# LEDs.net
KiCad netlist of a schematic drawn in Altium Designer
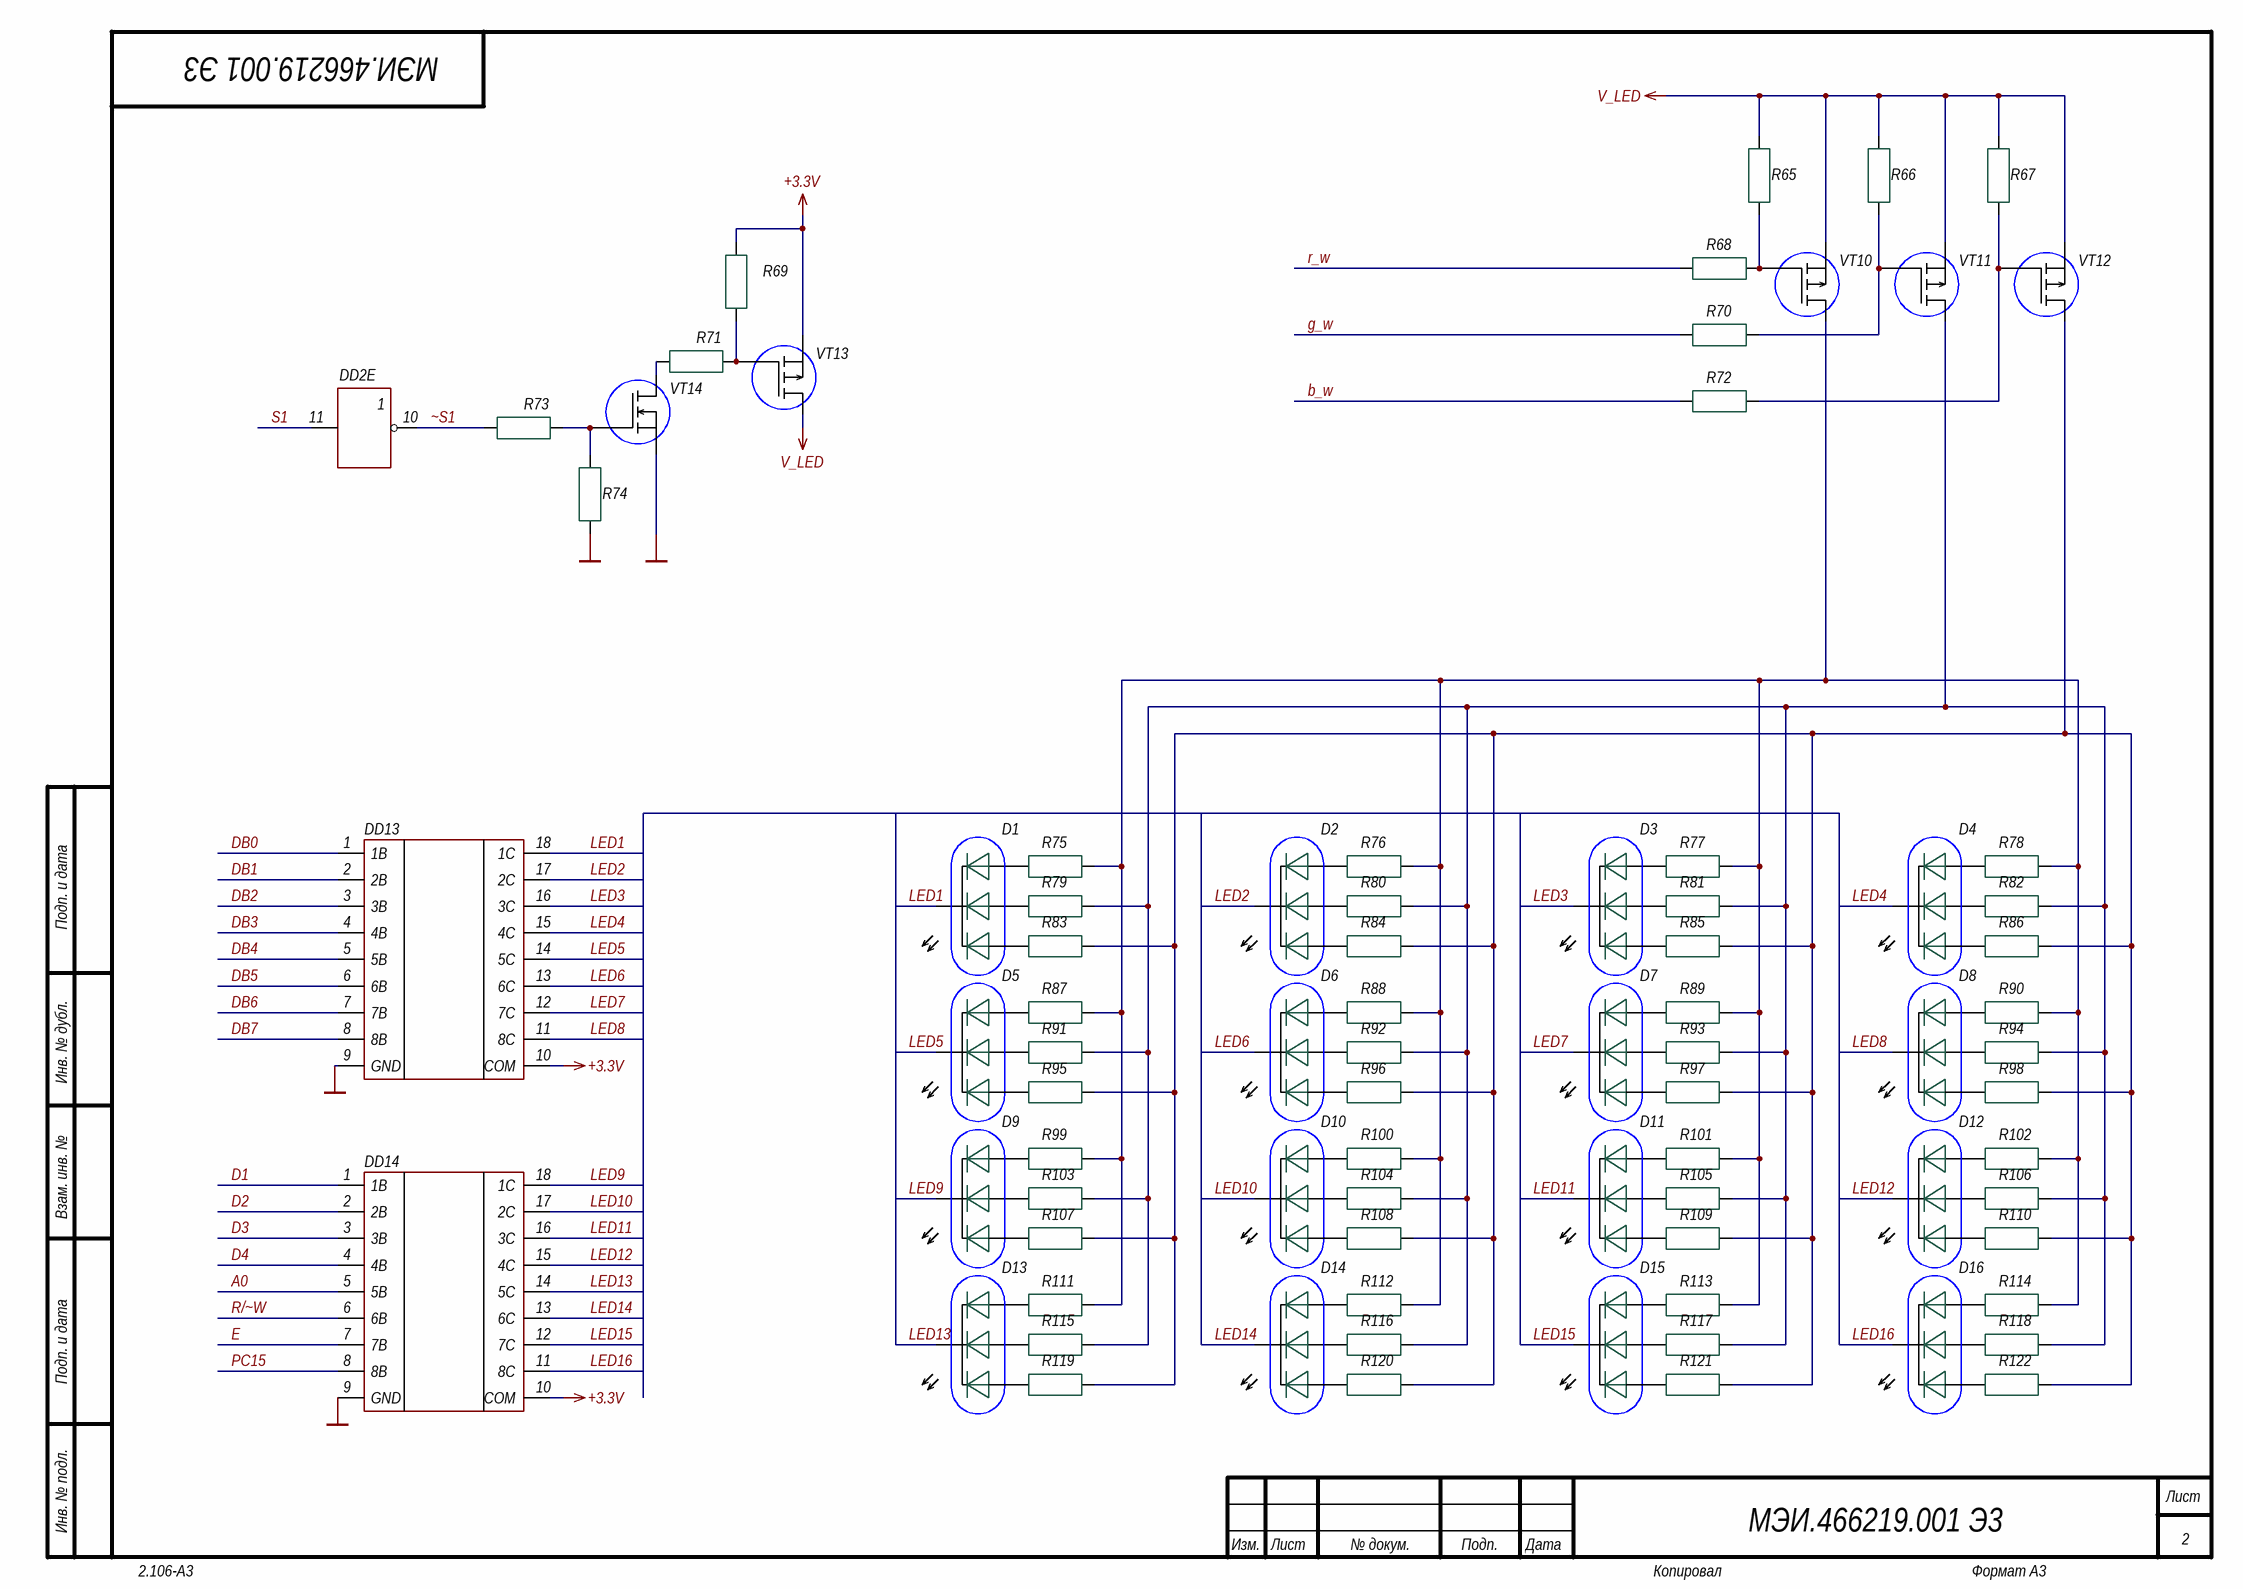
[diagram p0: LEDs.SchDoc]

(export (version "E")
  (design (tool "Eeschema 10.0.6"))
  (components
    (comp (ref "D1")
      (value "FYLS-5050RGBC")
      (footprint "LeSta:SOP6LED")
      (description "RGB LED")
      (libsource (lib "LeSta") (part "FYLS-5050RGBC"))
    )
    (comp (ref "D2")
      (value "FYLS-5050RGBC")
      (footprint "LeSta:SOP6LED")
      (description "RGB LED")
      (libsource (lib "LeSta") (part "FYLS-5050RGBC"))
    )
    (comp (ref "D3")
      (value "FYLS-5050RGBC")
      (footprint "LeSta:SOP6LED")
      (description "RGB LED")
      (libsource (lib "LeSta") (part "FYLS-5050RGBC"))
    )
    (comp (ref "D4")
      (value "FYLS-5050RGBC")
      (footprint "LeSta:SOP6LED")
      (description "RGB LED")
      (libsource (lib "LeSta") (part "FYLS-5050RGBC"))
    )
    (comp (ref "D5")
      (value "FYLS-5050RGBC")
      (footprint "LeSta:SOP6LED")
      (description "RGB LED")
      (libsource (lib "LeSta") (part "FYLS-5050RGBC"))
    )
    (comp (ref "D6")
      (value "FYLS-5050RGBC")
      (footprint "LeSta:SOP6LED")
      (description "RGB LED")
      (libsource (lib "LeSta") (part "FYLS-5050RGBC"))
    )
    (comp (ref "D7")
      (value "FYLS-5050RGBC")
      (footprint "LeSta:SOP6LED")
      (description "RGB LED")
      (libsource (lib "LeSta") (part "FYLS-5050RGBC"))
    )
    (comp (ref "D8")
      (value "FYLS-5050RGBC")
      (footprint "LeSta:SOP6LED")
      (description "RGB LED")
      (libsource (lib "LeSta") (part "FYLS-5050RGBC"))
    )
    (comp (ref "D9")
      (value "FYLS-5050RGBC")
      (footprint "LeSta:SOP6LED")
      (description "RGB LED")
      (libsource (lib "LeSta") (part "FYLS-5050RGBC"))
    )
    (comp (ref "D10")
      (value "FYLS-5050RGBC")
      (footprint "LeSta:SOP6LED")
      (description "RGB LED")
      (libsource (lib "LeSta") (part "FYLS-5050RGBC"))
    )
    (comp (ref "D11")
      (value "FYLS-5050RGBC")
      (footprint "LeSta:SOP6LED")
      (description "RGB LED")
      (libsource (lib "LeSta") (part "FYLS-5050RGBC"))
    )
    (comp (ref "D12")
      (value "FYLS-5050RGBC")
      (footprint "LeSta:SOP6LED")
      (description "RGB LED")
      (libsource (lib "LeSta") (part "FYLS-5050RGBC"))
    )
    (comp (ref "D13")
      (value "FYLS-5050RGBC")
      (footprint "LeSta:SOP6LED")
      (description "RGB LED")
      (libsource (lib "LeSta") (part "FYLS-5050RGBC"))
    )
    (comp (ref "D14")
      (value "FYLS-5050RGBC")
      (footprint "LeSta:SOP6LED")
      (description "RGB LED")
      (libsource (lib "LeSta") (part "FYLS-5050RGBC"))
    )
    (comp (ref "D15")
      (value "FYLS-5050RGBC")
      (footprint "LeSta:SOP6LED")
      (description "RGB LED")
      (libsource (lib "LeSta") (part "FYLS-5050RGBC"))
    )
    (comp (ref "D16")
      (value "FYLS-5050RGBC")
      (footprint "LeSta:SOP6LED")
      (description "RGB LED")
      (libsource (lib "LeSta") (part "FYLS-5050RGBC"))
    )
    (comp (ref "DD2")
      (value "SN74AHCU04DR")
      (footprint "PBL - SMD Packages:SOIC127P780X200-14N")
      (description "HEX invertor")
      (libsource (lib "LeSta") (part "SN74AHCU04"))
    )
    (comp (ref "DD13")
      (value "ULN2803ADW")
      (footprint "LeSta:SOIC127P600-8N")
      (description "Darlington Assembly")
      (libsource (lib "LeSta") (part "ULN2803"))
    )
    (comp (ref "DD14")
      (value "ULN2803ADW")
      (footprint "LeSta:SOIC127P600-8N")
      (description "Darlington Assembly")
      (libsource (lib "LeSta") (part "ULN2803"))
    )
    (comp (ref "R65")
      (value "Thick Film")
      (footprint "RESC1608X55N")
      (description "Resistor SMD chip 10k Ohm 0.1W 1% 0603")
      (fields (field (name "TOLERANCE") "±1%"))
      (libsource (lib "PBL - Resistors") (part "RES_10K_0603_1%"))
    )
    (comp (ref "R66")
      (value "Thick Film")
      (footprint "RESC1608X55N")
      (description "Resistor SMD chip 10k Ohm 0.1W 1% 0603")
      (fields (field (name "TOLERANCE") "±1%"))
      (libsource (lib "PBL - Resistors") (part "RES_10K_0603_1%"))
    )
    (comp (ref "R67")
      (value "Thick Film")
      (footprint "RESC1608X55N")
      (description "Resistor SMD chip 10k Ohm 0.1W 1% 0603")
      (fields (field (name "TOLERANCE") "±1%"))
      (libsource (lib "PBL - Resistors") (part "RES_10K_0603_1%"))
    )
    (comp (ref "R68")
      (value "Thick Film")
      (footprint "RESC1608X55N")
      (description "Resistor SMD chip 470 Ohm 0.1W 5% 0603")
      (fields (field (name "TOLERANCE") "±5%"))
      (libsource (lib "PBL - Resistors") (part "RES_470R_0603_5%"))
    )
    (comp (ref "R69")
      (value "Thick Film")
      (footprint "RESC1608X55N")
      (description "Resistor SMD chip 10k Ohm 0.1W 1% 0603")
      (fields (field (name "TOLERANCE") "±1%"))
      (libsource (lib "PBL - Resistors") (part "RES_10K_0603_1%"))
    )
    (comp (ref "R70")
      (value "Thick Film")
      (footprint "RESC1608X55N")
      (description "Resistor SMD chip 470 Ohm 0.1W 5% 0603")
      (fields (field (name "TOLERANCE") "±5%"))
      (libsource (lib "PBL - Resistors") (part "RES_470R_0603_5%"))
    )
    (comp (ref "R71")
      (value "Thick Film")
      (footprint "RESC1608X55N")
      (description "Resistor SMD chip 470 Ohm 0.1W 5% 0603")
      (fields (field (name "TOLERANCE") "±5%"))
      (libsource (lib "PBL - Resistors") (part "RES_470R_0603_5%"))
    )
    (comp (ref "R72")
      (value "Thick Film")
      (footprint "RESC1608X55N")
      (description "Resistor SMD chip 470 Ohm 0.1W 5% 0603")
      (fields (field (name "TOLERANCE") "±5%"))
      (libsource (lib "PBL - Resistors") (part "RES_470R_0603_5%"))
    )
    (comp (ref "R73")
      (value "Thick Film")
      (footprint "RESC1608X55N")
      (description "Resistor SMD chip 470 Ohm 0.1W 5% 0603")
      (fields (field (name "TOLERANCE") "±5%"))
      (libsource (lib "PBL - Resistors") (part "RES_470R_0603_5%"))
    )
    (comp (ref "R74")
      (value "Thick Film")
      (footprint "RESC1608X55N")
      (description "Resistor SMD chip 10k Ohm 0.1W 1% 0603")
      (fields (field (name "TOLERANCE") "±1%"))
      (libsource (lib "PBL - Resistors") (part "RES_10K_0603_1%"))
    )
    (comp (ref "R75")
      (value "Thick Film")
      (footprint "RESC1608X55N")
      (description "Resistor SMD chip 1,2 kOhm 0.1W 1% 0603")
      (fields (field (name "TOLERANCE") "±1%"))
      (libsource (lib "LearningStand") (part "RES_1K2_0603_1%"))
    )
    (comp (ref "R76")
      (value "Thick Film")
      (footprint "RESC1608X55N")
      (description "Resistor SMD chip 1,2 kOhm 0.1W 1% 0603")
      (fields (field (name "TOLERANCE") "±1%"))
      (libsource (lib "LearningStand") (part "RES_1K2_0603_1%"))
    )
    (comp (ref "R77")
      (value "Thick Film")
      (footprint "RESC1608X55N")
      (description "Resistor SMD chip 1,2 kOhm 0.1W 1% 0603")
      (fields (field (name "TOLERANCE") "±1%"))
      (libsource (lib "LearningStand") (part "RES_1K2_0603_1%"))
    )
    (comp (ref "R78")
      (value "Thick Film")
      (footprint "RESC1608X55N")
      (description "Resistor SMD chip 1,2 kOhm 0.1W 1% 0603")
      (fields (field (name "TOLERANCE") "±1%"))
      (libsource (lib "LearningStand") (part "RES_1K2_0603_1%"))
    )
    (comp (ref "R79")
      (value "Thick Film")
      (footprint "RESC1608X55N")
      (description "Resistor SMD chip 1,2 kOhm 0.1W 1% 0603")
      (fields (field (name "TOLERANCE") "±1%"))
      (libsource (lib "LearningStand") (part "RES_1K2_0603_1%"))
    )
    (comp (ref "R80")
      (value "Thick Film")
      (footprint "RESC1608X55N")
      (description "Resistor SMD chip 1,2 kOhm 0.1W 1% 0603")
      (fields (field (name "TOLERANCE") "±1%"))
      (libsource (lib "LearningStand") (part "RES_1K2_0603_1%"))
    )
    (comp (ref "R81")
      (value "Thick Film")
      (footprint "RESC1608X55N")
      (description "Resistor SMD chip 1,2 kOhm 0.1W 1% 0603")
      (fields (field (name "TOLERANCE") "±1%"))
      (libsource (lib "LearningStand") (part "RES_1K2_0603_1%"))
    )
    (comp (ref "R82")
      (value "Thick Film")
      (footprint "RESC1608X55N")
      (description "Resistor SMD chip 1,2 kOhm 0.1W 1% 0603")
      (fields (field (name "TOLERANCE") "±1%"))
      (libsource (lib "LearningStand") (part "RES_1K2_0603_1%"))
    )
    (comp (ref "R83")
      (value "Thick Film")
      (footprint "RESC1608X55N")
      (description "Resistor SMD chip 1,2 kOhm 0.1W 1% 0603")
      (fields (field (name "TOLERANCE") "±1%"))
      (libsource (lib "LearningStand") (part "RES_1K2_0603_1%"))
    )
    (comp (ref "R84")
      (value "Thick Film")
      (footprint "RESC1608X55N")
      (description "Resistor SMD chip 1,2 kOhm 0.1W 1% 0603")
      (fields (field (name "TOLERANCE") "±1%"))
      (libsource (lib "LearningStand") (part "RES_1K2_0603_1%"))
    )
    (comp (ref "R85")
      (value "Thick Film")
      (footprint "RESC1608X55N")
      (description "Resistor SMD chip 1,2 kOhm 0.1W 1% 0603")
      (fields (field (name "TOLERANCE") "±1%"))
      (libsource (lib "LearningStand") (part "RES_1K2_0603_1%"))
    )
    (comp (ref "R86")
      (value "Thick Film")
      (footprint "RESC1608X55N")
      (description "Resistor SMD chip 1,2 kOhm 0.1W 1% 0603")
      (fields (field (name "TOLERANCE") "±1%"))
      (libsource (lib "LearningStand") (part "RES_1K2_0603_1%"))
    )
    (comp (ref "R87")
      (value "Thick Film")
      (footprint "RESC1608X55N")
      (description "Resistor SMD chip 1,2 kOhm 0.1W 1% 0603")
      (fields (field (name "TOLERANCE") "±1%"))
      (libsource (lib "LearningStand") (part "RES_1K2_0603_1%"))
    )
    (comp (ref "R88")
      (value "Thick Film")
      (footprint "RESC1608X55N")
      (description "Resistor SMD chip 1,2 kOhm 0.1W 1% 0603")
      (fields (field (name "TOLERANCE") "±1%"))
      (libsource (lib "LearningStand") (part "RES_1K2_0603_1%"))
    )
    (comp (ref "R89")
      (value "Thick Film")
      (footprint "RESC1608X55N")
      (description "Resistor SMD chip 1,2 kOhm 0.1W 1% 0603")
      (fields (field (name "TOLERANCE") "±1%"))
      (libsource (lib "LearningStand") (part "RES_1K2_0603_1%"))
    )
    (comp (ref "R90")
      (value "Thick Film")
      (footprint "RESC1608X55N")
      (description "Resistor SMD chip 1,2 kOhm 0.1W 1% 0603")
      (fields (field (name "TOLERANCE") "±1%"))
      (libsource (lib "LearningStand") (part "RES_1K2_0603_1%"))
    )
    (comp (ref "R91")
      (value "Thick Film")
      (footprint "RESC1608X55N")
      (description "Resistor SMD chip 1,2 kOhm 0.1W 1% 0603")
      (fields (field (name "TOLERANCE") "±1%"))
      (libsource (lib "LearningStand") (part "RES_1K2_0603_1%"))
    )
    (comp (ref "R92")
      (value "Thick Film")
      (footprint "RESC1608X55N")
      (description "Resistor SMD chip 1,2 kOhm 0.1W 1% 0603")
      (fields (field (name "TOLERANCE") "±1%"))
      (libsource (lib "LearningStand") (part "RES_1K2_0603_1%"))
    )
    (comp (ref "R93")
      (value "Thick Film")
      (footprint "RESC1608X55N")
      (description "Resistor SMD chip 1,2 kOhm 0.1W 1% 0603")
      (fields (field (name "TOLERANCE") "±1%"))
      (libsource (lib "LearningStand") (part "RES_1K2_0603_1%"))
    )
    (comp (ref "R94")
      (value "Thick Film")
      (footprint "RESC1608X55N")
      (description "Resistor SMD chip 1,2 kOhm 0.1W 1% 0603")
      (fields (field (name "TOLERANCE") "±1%"))
      (libsource (lib "LearningStand") (part "RES_1K2_0603_1%"))
    )
    (comp (ref "R95")
      (value "Thick Film")
      (footprint "RESC1608X55N")
      (description "Resistor SMD chip 1,2 kOhm 0.1W 1% 0603")
      (fields (field (name "TOLERANCE") "±1%"))
      (libsource (lib "LearningStand") (part "RES_1K2_0603_1%"))
    )
    (comp (ref "R96")
      (value "Thick Film")
      (footprint "RESC1608X55N")
      (description "Resistor SMD chip 1,2 kOhm 0.1W 1% 0603")
      (fields (field (name "TOLERANCE") "±1%"))
      (libsource (lib "LearningStand") (part "RES_1K2_0603_1%"))
    )
    (comp (ref "R97")
      (value "Thick Film")
      (footprint "RESC1608X55N")
      (description "Resistor SMD chip 1,2 kOhm 0.1W 1% 0603")
      (fields (field (name "TOLERANCE") "±1%"))
      (libsource (lib "LearningStand") (part "RES_1K2_0603_1%"))
    )
    (comp (ref "R98")
      (value "Thick Film")
      (footprint "RESC1608X55N")
      (description "Resistor SMD chip 1,2 kOhm 0.1W 1% 0603")
      (fields (field (name "TOLERANCE") "±1%"))
      (libsource (lib "LearningStand") (part "RES_1K2_0603_1%"))
    )
    (comp (ref "R99")
      (value "Thick Film")
      (footprint "RESC1608X55N")
      (description "Resistor SMD chip 1,2 kOhm 0.1W 1% 0603")
      (fields (field (name "TOLERANCE") "±1%"))
      (libsource (lib "LearningStand") (part "RES_1K2_0603_1%"))
    )
    (comp (ref "R100")
      (value "Thick Film")
      (footprint "RESC1608X55N")
      (description "Resistor SMD chip 1,2 kOhm 0.1W 1% 0603")
      (fields (field (name "TOLERANCE") "±1%"))
      (libsource (lib "LearningStand") (part "RES_1K2_0603_1%"))
    )
    (comp (ref "R101")
      (value "Thick Film")
      (footprint "RESC1608X55N")
      (description "Resistor SMD chip 1,2 kOhm 0.1W 1% 0603")
      (fields (field (name "TOLERANCE") "±1%"))
      (libsource (lib "LearningStand") (part "RES_1K2_0603_1%"))
    )
    (comp (ref "R102")
      (value "Thick Film")
      (footprint "RESC1608X55N")
      (description "Resistor SMD chip 1,2 kOhm 0.1W 1% 0603")
      (fields (field (name "TOLERANCE") "±1%"))
      (libsource (lib "LearningStand") (part "RES_1K2_0603_1%"))
    )
    (comp (ref "R103")
      (value "Thick Film")
      (footprint "RESC1608X55N")
      (description "Resistor SMD chip 1,2 kOhm 0.1W 1% 0603")
      (fields (field (name "TOLERANCE") "±1%"))
      (libsource (lib "LearningStand") (part "RES_1K2_0603_1%"))
    )
    (comp (ref "R104")
      (value "Thick Film")
      (footprint "RESC1608X55N")
      (description "Resistor SMD chip 1,2 kOhm 0.1W 1% 0603")
      (fields (field (name "TOLERANCE") "±1%"))
      (libsource (lib "LearningStand") (part "RES_1K2_0603_1%"))
    )
    (comp (ref "R105")
      (value "Thick Film")
      (footprint "RESC1608X55N")
      (description "Resistor SMD chip 1,2 kOhm 0.1W 1% 0603")
      (fields (field (name "TOLERANCE") "±1%"))
      (libsource (lib "LearningStand") (part "RES_1K2_0603_1%"))
    )
    (comp (ref "R106")
      (value "Thick Film")
      (footprint "RESC1608X55N")
      (description "Resistor SMD chip 1,2 kOhm 0.1W 1% 0603")
      (fields (field (name "TOLERANCE") "±1%"))
      (libsource (lib "LearningStand") (part "RES_1K2_0603_1%"))
    )
    (comp (ref "R107")
      (value "Thick Film")
      (footprint "RESC1608X55N")
      (description "Resistor SMD chip 1,2 kOhm 0.1W 1% 0603")
      (fields (field (name "TOLERANCE") "±1%"))
      (libsource (lib "LearningStand") (part "RES_1K2_0603_1%"))
    )
    (comp (ref "R108")
      (value "Thick Film")
      (footprint "RESC1608X55N")
      (description "Resistor SMD chip 1,2 kOhm 0.1W 1% 0603")
      (fields (field (name "TOLERANCE") "±1%"))
      (libsource (lib "LearningStand") (part "RES_1K2_0603_1%"))
    )
    (comp (ref "R109")
      (value "Thick Film")
      (footprint "RESC1608X55N")
      (description "Resistor SMD chip 1,2 kOhm 0.1W 1% 0603")
      (fields (field (name "TOLERANCE") "±1%"))
      (libsource (lib "LearningStand") (part "RES_1K2_0603_1%"))
    )
    (comp (ref "R110")
      (value "Thick Film")
      (footprint "RESC1608X55N")
      (description "Resistor SMD chip 1,2 kOhm 0.1W 1% 0603")
      (fields (field (name "TOLERANCE") "±1%"))
      (libsource (lib "LearningStand") (part "RES_1K2_0603_1%"))
    )
    (comp (ref "R111")
      (value "Thick Film")
      (footprint "RESC1608X55N")
      (description "Resistor SMD chip 1,2 kOhm 0.1W 1% 0603")
      (fields (field (name "TOLERANCE") "±1%"))
      (libsource (lib "LearningStand") (part "RES_1K2_0603_1%"))
    )
    (comp (ref "R112")
      (value "Thick Film")
      (footprint "RESC1608X55N")
      (description "Resistor SMD chip 1,2 kOhm 0.1W 1% 0603")
      (fields (field (name "TOLERANCE") "±1%"))
      (libsource (lib "LearningStand") (part "RES_1K2_0603_1%"))
    )
    (comp (ref "R113")
      (value "Thick Film")
      (footprint "RESC1608X55N")
      (description "Resistor SMD chip 1,2 kOhm 0.1W 1% 0603")
      (fields (field (name "TOLERANCE") "±1%"))
      (libsource (lib "LearningStand") (part "RES_1K2_0603_1%"))
    )
    (comp (ref "R114")
      (value "Thick Film")
      (footprint "RESC1608X55N")
      (description "Resistor SMD chip 1,2 kOhm 0.1W 1% 0603")
      (fields (field (name "TOLERANCE") "±1%"))
      (libsource (lib "LearningStand") (part "RES_1K2_0603_1%"))
    )
    (comp (ref "R115")
      (value "Thick Film")
      (footprint "RESC1608X55N")
      (description "Resistor SMD chip 1,2 kOhm 0.1W 1% 0603")
      (fields (field (name "TOLERANCE") "±1%"))
      (libsource (lib "LearningStand") (part "RES_1K2_0603_1%"))
    )
    (comp (ref "R116")
      (value "Thick Film")
      (footprint "RESC1608X55N")
      (description "Resistor SMD chip 1,2 kOhm 0.1W 1% 0603")
      (fields (field (name "TOLERANCE") "±1%"))
      (libsource (lib "LearningStand") (part "RES_1K2_0603_1%"))
    )
    (comp (ref "R117")
      (value "Thick Film")
      (footprint "RESC1608X55N")
      (description "Resistor SMD chip 1,2 kOhm 0.1W 1% 0603")
      (fields (field (name "TOLERANCE") "±1%"))
      (libsource (lib "LearningStand") (part "RES_1K2_0603_1%"))
    )
    (comp (ref "R118")
      (value "Thick Film")
      (footprint "RESC1608X55N")
      (description "Resistor SMD chip 1,2 kOhm 0.1W 1% 0603")
      (fields (field (name "TOLERANCE") "±1%"))
      (libsource (lib "LearningStand") (part "RES_1K2_0603_1%"))
    )
    (comp (ref "R119")
      (value "Thick Film")
      (footprint "RESC1608X55N")
      (description "Resistor SMD chip 1,2 kOhm 0.1W 1% 0603")
      (fields (field (name "TOLERANCE") "±1%"))
      (libsource (lib "LearningStand") (part "RES_1K2_0603_1%"))
    )
    (comp (ref "R120")
      (value "Thick Film")
      (footprint "RESC1608X55N")
      (description "Resistor SMD chip 1,2 kOhm 0.1W 1% 0603")
      (fields (field (name "TOLERANCE") "±1%"))
      (libsource (lib "LearningStand") (part "RES_1K2_0603_1%"))
    )
    (comp (ref "R121")
      (value "Thick Film")
      (footprint "RESC1608X55N")
      (description "Resistor SMD chip 1,2 kOhm 0.1W 1% 0603")
      (fields (field (name "TOLERANCE") "±1%"))
      (libsource (lib "LearningStand") (part "RES_1K2_0603_1%"))
    )
    (comp (ref "R122")
      (value "Thick Film")
      (footprint "RESC1608X55N")
      (description "Resistor SMD chip 1,2 kOhm 0.1W 1% 0603")
      (fields (field (name "TOLERANCE") "±1%"))
      (libsource (lib "LearningStand") (part "RES_1K2_0603_1%"))
    )
    (comp (ref "VT10")
      (value "IRLML2244")
      (footprint "PBL - SMD Packages:SOT23-3-no_check")
      (description "MOSFET P-Channel SMD")
      (libsource (lib "PBL - Transistors") (part "MOSFET_P-CH_IRLML2244TRPbF"))
    )
    (comp (ref "VT11")
      (value "IRLML2244")
      (footprint "PBL - SMD Packages:SOT23-3-no_check")
      (description "MOSFET P-Channel SMD")
      (libsource (lib "PBL - Transistors") (part "MOSFET_P-CH_IRLML2244TRPbF"))
    )
    (comp (ref "VT12")
      (value "IRLML2244")
      (footprint "PBL - SMD Packages:SOT23-3-no_check")
      (description "MOSFET P-Channel SMD")
      (libsource (lib "PBL - Transistors") (part "MOSFET_P-CH_IRLML2244TRPbF"))
    )
    (comp (ref "VT13")
      (value "IRLML2244")
      (footprint "PBL - SMD Packages:SOT23-3-no_check")
      (description "MOSFET P-Channel SMD")
      (libsource (lib "PBL - Transistors") (part "MOSFET_P-CH_IRLML2244TRPbF"))
    )
    (comp (ref "VT14")
      (value "IRLML6244")
      (footprint "PBL - SMD Packages:SOT23-3-no_check")
      (description "MOSFET N-Channel SMD")
      (libsource (lib "PBL - Transistors") (part "MOSFET_N-CH_IRLML6244TRPBF"))
    )
  )
  (nets
    (net (code "1") (name "+3.3V") (class "Default")
      (node (ref "DD13") (pin "10") (pinfunction "COM_10") (pintype "passive"))
      (node (ref "DD14") (pin "10") (pinfunction "COM_10") (pintype "passive"))
      (node (ref "R69") (pin "2") (pinfunction "2_2") (pintype "passive"))
      (node (ref "VT13") (pin "2") (pinfunction "S_2") (pintype "passive"))
    )
    (net (code "2") (name "/A0") (class "Default")
      (node (ref "DD14") (pin "5") (pinfunction "5B_5") (pintype "passive"))
    )
    (net (code "3") (name "/D1") (class "Default")
      (node (ref "DD14") (pin "1") (pinfunction "1B_1") (pintype "passive"))
    )
    (net (code "4") (name "/D2") (class "Default")
      (node (ref "DD14") (pin "2") (pinfunction "2B_2") (pintype "passive"))
    )
    (net (code "5") (name "/D3") (class "Default")
      (node (ref "DD14") (pin "3") (pinfunction "3B_3") (pintype "passive"))
    )
    (net (code "6") (name "/D4") (class "Default")
      (node (ref "DD14") (pin "4") (pinfunction "4B_4") (pintype "passive"))
    )
    (net (code "7") (name "/DB0") (class "Default")
      (node (ref "DD13") (pin "1") (pinfunction "1B_1") (pintype "passive"))
    )
    (net (code "8") (name "/DB1") (class "Default")
      (node (ref "DD13") (pin "2") (pinfunction "2B_2") (pintype "passive"))
    )
    (net (code "9") (name "/DB2") (class "Default")
      (node (ref "DD13") (pin "3") (pinfunction "3B_3") (pintype "passive"))
    )
    (net (code "10") (name "/DB3") (class "Default")
      (node (ref "DD13") (pin "4") (pinfunction "4B_4") (pintype "passive"))
    )
    (net (code "11") (name "/DB4") (class "Default")
      (node (ref "DD13") (pin "5") (pinfunction "5B_5") (pintype "passive"))
    )
    (net (code "12") (name "/DB5") (class "Default")
      (node (ref "DD13") (pin "6") (pinfunction "6B_6") (pintype "passive"))
    )
    (net (code "13") (name "/DB6") (class "Default")
      (node (ref "DD13") (pin "7") (pinfunction "7B_7") (pintype "passive"))
    )
    (net (code "14") (name "/DB7") (class "Default")
      (node (ref "DD13") (pin "8") (pinfunction "8B_8") (pintype "passive"))
    )
    (net (code "15") (name "/E") (class "Default")
      (node (ref "DD14") (pin "7") (pinfunction "7B_7") (pintype "passive"))
    )
    (net (code "16") (name "/LED1") (class "Default")
      (node (ref "D1") (pin "K") (pinfunction "K_K") (pintype "passive"))
      (node (ref "DD13") (pin "18") (pinfunction "1C_18") (pintype "passive"))
    )
    (net (code "17") (name "/LED2") (class "Default")
      (node (ref "D2") (pin "K") (pinfunction "K_K") (pintype "passive"))
      (node (ref "DD13") (pin "17") (pinfunction "2C_17") (pintype "passive"))
    )
    (net (code "18") (name "/LED3") (class "Default")
      (node (ref "D3") (pin "K") (pinfunction "K_K") (pintype "passive"))
      (node (ref "DD13") (pin "16") (pinfunction "3C_16") (pintype "passive"))
    )
    (net (code "19") (name "/LED4") (class "Default")
      (node (ref "D4") (pin "K") (pinfunction "K_K") (pintype "passive"))
      (node (ref "DD13") (pin "15") (pinfunction "4C_15") (pintype "passive"))
    )
    (net (code "20") (name "/LED5") (class "Default")
      (node (ref "D5") (pin "K") (pinfunction "K_K") (pintype "passive"))
      (node (ref "DD13") (pin "14") (pinfunction "5C_14") (pintype "passive"))
    )
    (net (code "21") (name "/LED6") (class "Default")
      (node (ref "D6") (pin "K") (pinfunction "K_K") (pintype "passive"))
      (node (ref "DD13") (pin "13") (pinfunction "6C_13") (pintype "passive"))
    )
    (net (code "22") (name "/LED7") (class "Default")
      (node (ref "D7") (pin "K") (pinfunction "K_K") (pintype "passive"))
      (node (ref "DD13") (pin "12") (pinfunction "7C_12") (pintype "passive"))
    )
    (net (code "23") (name "/LED8") (class "Default")
      (node (ref "D8") (pin "K") (pinfunction "K_K") (pintype "passive"))
      (node (ref "DD13") (pin "11") (pinfunction "8C_11") (pintype "passive"))
    )
    (net (code "24") (name "/LED9") (class "Default")
      (node (ref "D9") (pin "K") (pinfunction "K_K") (pintype "passive"))
      (node (ref "DD14") (pin "18") (pinfunction "1C_18") (pintype "passive"))
    )
    (net (code "25") (name "/LED10") (class "Default")
      (node (ref "D10") (pin "K") (pinfunction "K_K") (pintype "passive"))
      (node (ref "DD14") (pin "17") (pinfunction "2C_17") (pintype "passive"))
    )
    (net (code "26") (name "/LED11") (class "Default")
      (node (ref "D11") (pin "K") (pinfunction "K_K") (pintype "passive"))
      (node (ref "DD14") (pin "16") (pinfunction "3C_16") (pintype "passive"))
    )
    (net (code "27") (name "/LED12") (class "Default")
      (node (ref "D12") (pin "K") (pinfunction "K_K") (pintype "passive"))
      (node (ref "DD14") (pin "15") (pinfunction "4C_15") (pintype "passive"))
    )
    (net (code "28") (name "/LED13") (class "Default")
      (node (ref "D13") (pin "K") (pinfunction "K_K") (pintype "passive"))
      (node (ref "DD14") (pin "14") (pinfunction "5C_14") (pintype "passive"))
    )
    (net (code "29") (name "/LED14") (class "Default")
      (node (ref "D14") (pin "K") (pinfunction "K_K") (pintype "passive"))
      (node (ref "DD14") (pin "13") (pinfunction "6C_13") (pintype "passive"))
    )
    (net (code "30") (name "/LED15") (class "Default")
      (node (ref "D15") (pin "K") (pinfunction "K_K") (pintype "passive"))
      (node (ref "DD14") (pin "12") (pinfunction "7C_12") (pintype "passive"))
    )
    (net (code "31") (name "/LED16") (class "Default")
      (node (ref "D16") (pin "K") (pinfunction "K_K") (pintype "passive"))
      (node (ref "DD14") (pin "11") (pinfunction "8C_11") (pintype "passive"))
    )
    (net (code "32") (name "/PC15") (class "Default")
      (node (ref "DD14") (pin "8") (pinfunction "8B_8") (pintype "passive"))
    )
    (net (code "33") (name "/R{slash}~W") (class "Default")
      (node (ref "DD14") (pin "6") (pinfunction "6B_6") (pintype "passive"))
    )
    (net (code "34") (name "/S1") (class "Default")
      (node (ref "DD2") (pin "11") (pinfunction "5A_11") (pintype "passive"))
    )
    (net (code "35") (name "/b_w") (class "Default")
      (node (ref "R72") (pin "1") (pinfunction "1_1") (pintype "passive"))
    )
    (net (code "36") (name "/g_w") (class "Default")
      (node (ref "R70") (pin "1") (pinfunction "1_1") (pintype "passive"))
    )
    (net (code "37") (name "/r_w") (class "Default")
      (node (ref "R68") (pin "1") (pinfunction "1_1") (pintype "passive"))
    )
    (net (code "38") (name "/~S1") (class "Default")
      (node (ref "DD2") (pin "10") (pinfunction "5Y_10") (pintype "passive"))
      (node (ref "R73") (pin "1") (pinfunction "1_1") (pintype "passive"))
    )
    (net (code "39") (name "GND") (class "Default")
      (node (ref "DD13") (pin "9") (pinfunction "GND_9") (pintype "passive"))
      (node (ref "DD14") (pin "9") (pinfunction "GND_9") (pintype "passive"))
      (node (ref "R74") (pin "1") (pinfunction "1_1") (pintype "passive"))
      (node (ref "VT14") (pin "2") (pinfunction "S_2") (pintype "passive"))
    )
    (net (code "40") (name "Net-(D1-PadAB)") (class "Default")
      (node (ref "D1") (pin "AB") (pinfunction "AB_AB") (pintype "passive"))
      (node (ref "R83") (pin "1") (pinfunction "1_1") (pintype "passive"))
    )
    (net (code "41") (name "Net-(D1-PadAG)") (class "Default")
      (node (ref "D1") (pin "AG") (pinfunction "AG_AG") (pintype "passive"))
      (node (ref "R79") (pin "1") (pinfunction "1_1") (pintype "passive"))
    )
    (net (code "42") (name "Net-(D1-PadAR)") (class "Default")
      (node (ref "D1") (pin "AR") (pinfunction "AR_AR") (pintype "passive"))
      (node (ref "R75") (pin "1") (pinfunction "1_1") (pintype "passive"))
    )
    (net (code "43") (name "Net-(D2-PadAB)") (class "Default")
      (node (ref "D2") (pin "AB") (pinfunction "AB_AB") (pintype "passive"))
      (node (ref "R84") (pin "1") (pinfunction "1_1") (pintype "passive"))
    )
    (net (code "44") (name "Net-(D2-PadAG)") (class "Default")
      (node (ref "D2") (pin "AG") (pinfunction "AG_AG") (pintype "passive"))
      (node (ref "R80") (pin "1") (pinfunction "1_1") (pintype "passive"))
    )
    (net (code "45") (name "Net-(D2-PadAR)") (class "Default")
      (node (ref "D2") (pin "AR") (pinfunction "AR_AR") (pintype "passive"))
      (node (ref "R76") (pin "1") (pinfunction "1_1") (pintype "passive"))
    )
    (net (code "46") (name "Net-(D3-PadAB)") (class "Default")
      (node (ref "D3") (pin "AB") (pinfunction "AB_AB") (pintype "passive"))
      (node (ref "R85") (pin "1") (pinfunction "1_1") (pintype "passive"))
    )
    (net (code "47") (name "Net-(D3-PadAG)") (class "Default")
      (node (ref "D3") (pin "AG") (pinfunction "AG_AG") (pintype "passive"))
      (node (ref "R81") (pin "1") (pinfunction "1_1") (pintype "passive"))
    )
    (net (code "48") (name "Net-(D3-PadAR)") (class "Default")
      (node (ref "D3") (pin "AR") (pinfunction "AR_AR") (pintype "passive"))
      (node (ref "R77") (pin "1") (pinfunction "1_1") (pintype "passive"))
    )
    (net (code "49") (name "Net-(D4-PadAB)") (class "Default")
      (node (ref "D4") (pin "AB") (pinfunction "AB_AB") (pintype "passive"))
      (node (ref "R86") (pin "1") (pinfunction "1_1") (pintype "passive"))
    )
    (net (code "50") (name "Net-(D4-PadAG)") (class "Default")
      (node (ref "D4") (pin "AG") (pinfunction "AG_AG") (pintype "passive"))
      (node (ref "R82") (pin "1") (pinfunction "1_1") (pintype "passive"))
    )
    (net (code "51") (name "Net-(D4-PadAR)") (class "Default")
      (node (ref "D4") (pin "AR") (pinfunction "AR_AR") (pintype "passive"))
      (node (ref "R78") (pin "1") (pinfunction "1_1") (pintype "passive"))
    )
    (net (code "52") (name "Net-(D5-PadAB)") (class "Default")
      (node (ref "D5") (pin "AB") (pinfunction "AB_AB") (pintype "passive"))
      (node (ref "R95") (pin "1") (pinfunction "1_1") (pintype "passive"))
    )
    (net (code "53") (name "Net-(D5-PadAG)") (class "Default")
      (node (ref "D5") (pin "AG") (pinfunction "AG_AG") (pintype "passive"))
      (node (ref "R91") (pin "1") (pinfunction "1_1") (pintype "passive"))
    )
    (net (code "54") (name "Net-(D5-PadAR)") (class "Default")
      (node (ref "D5") (pin "AR") (pinfunction "AR_AR") (pintype "passive"))
      (node (ref "R87") (pin "1") (pinfunction "1_1") (pintype "passive"))
    )
    (net (code "55") (name "Net-(D6-PadAB)") (class "Default")
      (node (ref "D6") (pin "AB") (pinfunction "AB_AB") (pintype "passive"))
      (node (ref "R96") (pin "1") (pinfunction "1_1") (pintype "passive"))
    )
    (net (code "56") (name "Net-(D6-PadAG)") (class "Default")
      (node (ref "D6") (pin "AG") (pinfunction "AG_AG") (pintype "passive"))
      (node (ref "R92") (pin "1") (pinfunction "1_1") (pintype "passive"))
    )
    (net (code "57") (name "Net-(D6-PadAR)") (class "Default")
      (node (ref "D6") (pin "AR") (pinfunction "AR_AR") (pintype "passive"))
      (node (ref "R88") (pin "1") (pinfunction "1_1") (pintype "passive"))
    )
    (net (code "58") (name "Net-(D7-PadAB)") (class "Default")
      (node (ref "D7") (pin "AB") (pinfunction "AB_AB") (pintype "passive"))
      (node (ref "R97") (pin "1") (pinfunction "1_1") (pintype "passive"))
    )
    (net (code "59") (name "Net-(D7-PadAG)") (class "Default")
      (node (ref "D7") (pin "AG") (pinfunction "AG_AG") (pintype "passive"))
      (node (ref "R93") (pin "1") (pinfunction "1_1") (pintype "passive"))
    )
    (net (code "60") (name "Net-(D7-PadAR)") (class "Default")
      (node (ref "D7") (pin "AR") (pinfunction "AR_AR") (pintype "passive"))
      (node (ref "R89") (pin "1") (pinfunction "1_1") (pintype "passive"))
    )
    (net (code "61") (name "Net-(D8-PadAB)") (class "Default")
      (node (ref "D8") (pin "AB") (pinfunction "AB_AB") (pintype "passive"))
      (node (ref "R98") (pin "1") (pinfunction "1_1") (pintype "passive"))
    )
    (net (code "62") (name "Net-(D8-PadAG)") (class "Default")
      (node (ref "D8") (pin "AG") (pinfunction "AG_AG") (pintype "passive"))
      (node (ref "R94") (pin "1") (pinfunction "1_1") (pintype "passive"))
    )
    (net (code "63") (name "Net-(D8-PadAR)") (class "Default")
      (node (ref "D8") (pin "AR") (pinfunction "AR_AR") (pintype "passive"))
      (node (ref "R90") (pin "1") (pinfunction "1_1") (pintype "passive"))
    )
    (net (code "64") (name "Net-(D9-PadAB)") (class "Default")
      (node (ref "D9") (pin "AB") (pinfunction "AB_AB") (pintype "passive"))
      (node (ref "R107") (pin "1") (pinfunction "1_1") (pintype "passive"))
    )
    (net (code "65") (name "Net-(D9-PadAG)") (class "Default")
      (node (ref "D9") (pin "AG") (pinfunction "AG_AG") (pintype "passive"))
      (node (ref "R103") (pin "1") (pinfunction "1_1") (pintype "passive"))
    )
    (net (code "66") (name "Net-(D9-PadAR)") (class "Default")
      (node (ref "D9") (pin "AR") (pinfunction "AR_AR") (pintype "passive"))
      (node (ref "R99") (pin "1") (pinfunction "1_1") (pintype "passive"))
    )
    (net (code "67") (name "Net-(D10-PadAB)") (class "Default")
      (node (ref "D10") (pin "AB") (pinfunction "AB_AB") (pintype "passive"))
      (node (ref "R108") (pin "1") (pinfunction "1_1") (pintype "passive"))
    )
    (net (code "68") (name "Net-(D10-PadAG)") (class "Default")
      (node (ref "D10") (pin "AG") (pinfunction "AG_AG") (pintype "passive"))
      (node (ref "R104") (pin "1") (pinfunction "1_1") (pintype "passive"))
    )
    (net (code "69") (name "Net-(D10-PadAR)") (class "Default")
      (node (ref "D10") (pin "AR") (pinfunction "AR_AR") (pintype "passive"))
      (node (ref "R100") (pin "1") (pinfunction "1_1") (pintype "passive"))
    )
    (net (code "70") (name "Net-(D11-PadAB)") (class "Default")
      (node (ref "D11") (pin "AB") (pinfunction "AB_AB") (pintype "passive"))
      (node (ref "R109") (pin "1") (pinfunction "1_1") (pintype "passive"))
    )
    (net (code "71") (name "Net-(D11-PadAG)") (class "Default")
      (node (ref "D11") (pin "AG") (pinfunction "AG_AG") (pintype "passive"))
      (node (ref "R105") (pin "1") (pinfunction "1_1") (pintype "passive"))
    )
    (net (code "72") (name "Net-(D11-PadAR)") (class "Default")
      (node (ref "D11") (pin "AR") (pinfunction "AR_AR") (pintype "passive"))
      (node (ref "R101") (pin "1") (pinfunction "1_1") (pintype "passive"))
    )
    (net (code "73") (name "Net-(D12-PadAB)") (class "Default")
      (node (ref "D12") (pin "AB") (pinfunction "AB_AB") (pintype "passive"))
      (node (ref "R110") (pin "1") (pinfunction "1_1") (pintype "passive"))
    )
    (net (code "74") (name "Net-(D12-PadAG)") (class "Default")
      (node (ref "D12") (pin "AG") (pinfunction "AG_AG") (pintype "passive"))
      (node (ref "R106") (pin "1") (pinfunction "1_1") (pintype "passive"))
    )
    (net (code "75") (name "Net-(D12-PadAR)") (class "Default")
      (node (ref "D12") (pin "AR") (pinfunction "AR_AR") (pintype "passive"))
      (node (ref "R102") (pin "1") (pinfunction "1_1") (pintype "passive"))
    )
    (net (code "76") (name "Net-(D13-PadAB)") (class "Default")
      (node (ref "D13") (pin "AB") (pinfunction "AB_AB") (pintype "passive"))
      (node (ref "R119") (pin "1") (pinfunction "1_1") (pintype "passive"))
    )
    (net (code "77") (name "Net-(D13-PadAG)") (class "Default")
      (node (ref "D13") (pin "AG") (pinfunction "AG_AG") (pintype "passive"))
      (node (ref "R115") (pin "1") (pinfunction "1_1") (pintype "passive"))
    )
    (net (code "78") (name "Net-(D13-PadAR)") (class "Default")
      (node (ref "D13") (pin "AR") (pinfunction "AR_AR") (pintype "passive"))
      (node (ref "R111") (pin "1") (pinfunction "1_1") (pintype "passive"))
    )
    (net (code "79") (name "Net-(D14-PadAB)") (class "Default")
      (node (ref "D14") (pin "AB") (pinfunction "AB_AB") (pintype "passive"))
      (node (ref "R120") (pin "1") (pinfunction "1_1") (pintype "passive"))
    )
    (net (code "80") (name "Net-(D14-PadAG)") (class "Default")
      (node (ref "D14") (pin "AG") (pinfunction "AG_AG") (pintype "passive"))
      (node (ref "R116") (pin "1") (pinfunction "1_1") (pintype "passive"))
    )
    (net (code "81") (name "Net-(D14-PadAR)") (class "Default")
      (node (ref "D14") (pin "AR") (pinfunction "AR_AR") (pintype "passive"))
      (node (ref "R112") (pin "1") (pinfunction "1_1") (pintype "passive"))
    )
    (net (code "82") (name "Net-(D15-PadAB)") (class "Default")
      (node (ref "D15") (pin "AB") (pinfunction "AB_AB") (pintype "passive"))
      (node (ref "R121") (pin "1") (pinfunction "1_1") (pintype "passive"))
    )
    (net (code "83") (name "Net-(D15-PadAG)") (class "Default")
      (node (ref "D15") (pin "AG") (pinfunction "AG_AG") (pintype "passive"))
      (node (ref "R117") (pin "1") (pinfunction "1_1") (pintype "passive"))
    )
    (net (code "84") (name "Net-(D15-PadAR)") (class "Default")
      (node (ref "D15") (pin "AR") (pinfunction "AR_AR") (pintype "passive"))
      (node (ref "R113") (pin "1") (pinfunction "1_1") (pintype "passive"))
    )
    (net (code "85") (name "Net-(D16-PadAB)") (class "Default")
      (node (ref "D16") (pin "AB") (pinfunction "AB_AB") (pintype "passive"))
      (node (ref "R122") (pin "1") (pinfunction "1_1") (pintype "passive"))
    )
    (net (code "86") (name "Net-(D16-PadAG)") (class "Default")
      (node (ref "D16") (pin "AG") (pinfunction "AG_AG") (pintype "passive"))
      (node (ref "R118") (pin "1") (pinfunction "1_1") (pintype "passive"))
    )
    (net (code "87") (name "Net-(D16-PadAR)") (class "Default")
      (node (ref "D16") (pin "AR") (pinfunction "AR_AR") (pintype "passive"))
      (node (ref "R114") (pin "1") (pinfunction "1_1") (pintype "passive"))
    )
    (net (code "88") (name "Net-(VT10-D)") (class "Default")
      (node (ref "R100") (pin "2") (pinfunction "2_2") (pintype "passive"))
      (node (ref "R101") (pin "2") (pinfunction "2_2") (pintype "passive"))
      (node (ref "R102") (pin "2") (pinfunction "2_2") (pintype "passive"))
      (node (ref "R111") (pin "2") (pinfunction "2_2") (pintype "passive"))
      (node (ref "R112") (pin "2") (pinfunction "2_2") (pintype "passive"))
      (node (ref "R113") (pin "2") (pinfunction "2_2") (pintype "passive"))
      (node (ref "R114") (pin "2") (pinfunction "2_2") (pintype "passive"))
      (node (ref "R75") (pin "2") (pinfunction "2_2") (pintype "passive"))
      (node (ref "R76") (pin "2") (pinfunction "2_2") (pintype "passive"))
      (node (ref "R77") (pin "2") (pinfunction "2_2") (pintype "passive"))
      (node (ref "R78") (pin "2") (pinfunction "2_2") (pintype "passive"))
      (node (ref "R87") (pin "2") (pinfunction "2_2") (pintype "passive"))
      (node (ref "R88") (pin "2") (pinfunction "2_2") (pintype "passive"))
      (node (ref "R89") (pin "2") (pinfunction "2_2") (pintype "passive"))
      (node (ref "R90") (pin "2") (pinfunction "2_2") (pintype "passive"))
      (node (ref "R99") (pin "2") (pinfunction "2_2") (pintype "passive"))
      (node (ref "VT10") (pin "3") (pinfunction "D_3") (pintype "passive"))
    )
    (net (code "89") (name "Net-(VT10-G)") (class "Default")
      (node (ref "R65") (pin "1") (pinfunction "1_1") (pintype "passive"))
      (node (ref "R68") (pin "2") (pinfunction "2_2") (pintype "passive"))
      (node (ref "VT10") (pin "1") (pinfunction "G_1") (pintype "passive"))
    )
    (net (code "90") (name "Net-(VT11-D)") (class "Default")
      (node (ref "R103") (pin "2") (pinfunction "2_2") (pintype "passive"))
      (node (ref "R104") (pin "2") (pinfunction "2_2") (pintype "passive"))
      (node (ref "R105") (pin "2") (pinfunction "2_2") (pintype "passive"))
      (node (ref "R106") (pin "2") (pinfunction "2_2") (pintype "passive"))
      (node (ref "R115") (pin "2") (pinfunction "2_2") (pintype "passive"))
      (node (ref "R116") (pin "2") (pinfunction "2_2") (pintype "passive"))
      (node (ref "R117") (pin "2") (pinfunction "2_2") (pintype "passive"))
      (node (ref "R118") (pin "2") (pinfunction "2_2") (pintype "passive"))
      (node (ref "R79") (pin "2") (pinfunction "2_2") (pintype "passive"))
      (node (ref "R80") (pin "2") (pinfunction "2_2") (pintype "passive"))
      (node (ref "R81") (pin "2") (pinfunction "2_2") (pintype "passive"))
      (node (ref "R82") (pin "2") (pinfunction "2_2") (pintype "passive"))
      (node (ref "R91") (pin "2") (pinfunction "2_2") (pintype "passive"))
      (node (ref "R92") (pin "2") (pinfunction "2_2") (pintype "passive"))
      (node (ref "R93") (pin "2") (pinfunction "2_2") (pintype "passive"))
      (node (ref "R94") (pin "2") (pinfunction "2_2") (pintype "passive"))
      (node (ref "VT11") (pin "3") (pinfunction "D_3") (pintype "passive"))
    )
    (net (code "91") (name "Net-(VT11-G)") (class "Default")
      (node (ref "R66") (pin "1") (pinfunction "1_1") (pintype "passive"))
      (node (ref "R70") (pin "2") (pinfunction "2_2") (pintype "passive"))
      (node (ref "VT11") (pin "1") (pinfunction "G_1") (pintype "passive"))
    )
    (net (code "92") (name "Net-(VT12-D)") (class "Default")
      (node (ref "R107") (pin "2") (pinfunction "2_2") (pintype "passive"))
      (node (ref "R108") (pin "2") (pinfunction "2_2") (pintype "passive"))
      (node (ref "R109") (pin "2") (pinfunction "2_2") (pintype "passive"))
      (node (ref "R110") (pin "2") (pinfunction "2_2") (pintype "passive"))
      (node (ref "R119") (pin "2") (pinfunction "2_2") (pintype "passive"))
      (node (ref "R120") (pin "2") (pinfunction "2_2") (pintype "passive"))
      (node (ref "R121") (pin "2") (pinfunction "2_2") (pintype "passive"))
      (node (ref "R122") (pin "2") (pinfunction "2_2") (pintype "passive"))
      (node (ref "R83") (pin "2") (pinfunction "2_2") (pintype "passive"))
      (node (ref "R84") (pin "2") (pinfunction "2_2") (pintype "passive"))
      (node (ref "R85") (pin "2") (pinfunction "2_2") (pintype "passive"))
      (node (ref "R86") (pin "2") (pinfunction "2_2") (pintype "passive"))
      (node (ref "R95") (pin "2") (pinfunction "2_2") (pintype "passive"))
      (node (ref "R96") (pin "2") (pinfunction "2_2") (pintype "passive"))
      (node (ref "R97") (pin "2") (pinfunction "2_2") (pintype "passive"))
      (node (ref "R98") (pin "2") (pinfunction "2_2") (pintype "passive"))
      (node (ref "VT12") (pin "3") (pinfunction "D_3") (pintype "passive"))
    )
    (net (code "93") (name "Net-(VT12-G)") (class "Default")
      (node (ref "R67") (pin "1") (pinfunction "1_1") (pintype "passive"))
      (node (ref "R72") (pin "2") (pinfunction "2_2") (pintype "passive"))
      (node (ref "VT12") (pin "1") (pinfunction "G_1") (pintype "passive"))
    )
    (net (code "94") (name "Net-(VT13-G)") (class "Default")
      (node (ref "R69") (pin "1") (pinfunction "1_1") (pintype "passive"))
      (node (ref "R71") (pin "2") (pinfunction "2_2") (pintype "passive"))
      (node (ref "VT13") (pin "1") (pinfunction "G_1") (pintype "passive"))
    )
    (net (code "95") (name "Net-(VT14-D)") (class "Default")
      (node (ref "R71") (pin "1") (pinfunction "1_1") (pintype "passive"))
      (node (ref "VT14") (pin "3") (pinfunction "D_3") (pintype "passive"))
    )
    (net (code "96") (name "Net-(VT14-G)") (class "Default")
      (node (ref "R73") (pin "2") (pinfunction "2_2") (pintype "passive"))
      (node (ref "R74") (pin "2") (pinfunction "2_2") (pintype "passive"))
      (node (ref "VT14") (pin "1") (pinfunction "G_1") (pintype "passive"))
    )
    (net (code "97") (name "V_LED") (class "Default")
      (node (ref "R65") (pin "2") (pinfunction "2_2") (pintype "passive"))
      (node (ref "R66") (pin "2") (pinfunction "2_2") (pintype "passive"))
      (node (ref "R67") (pin "2") (pinfunction "2_2") (pintype "passive"))
      (node (ref "VT10") (pin "2") (pinfunction "S_2") (pintype "passive"))
      (node (ref "VT11") (pin "2") (pinfunction "S_2") (pintype "passive"))
      (node (ref "VT12") (pin "2") (pinfunction "S_2") (pintype "passive"))
      (node (ref "VT13") (pin "3") (pinfunction "D_3") (pintype "passive"))
    )
  )
)
